# 03PERIPHERALS.net
KiCad netlist of a schematic drawn in Altium Designer
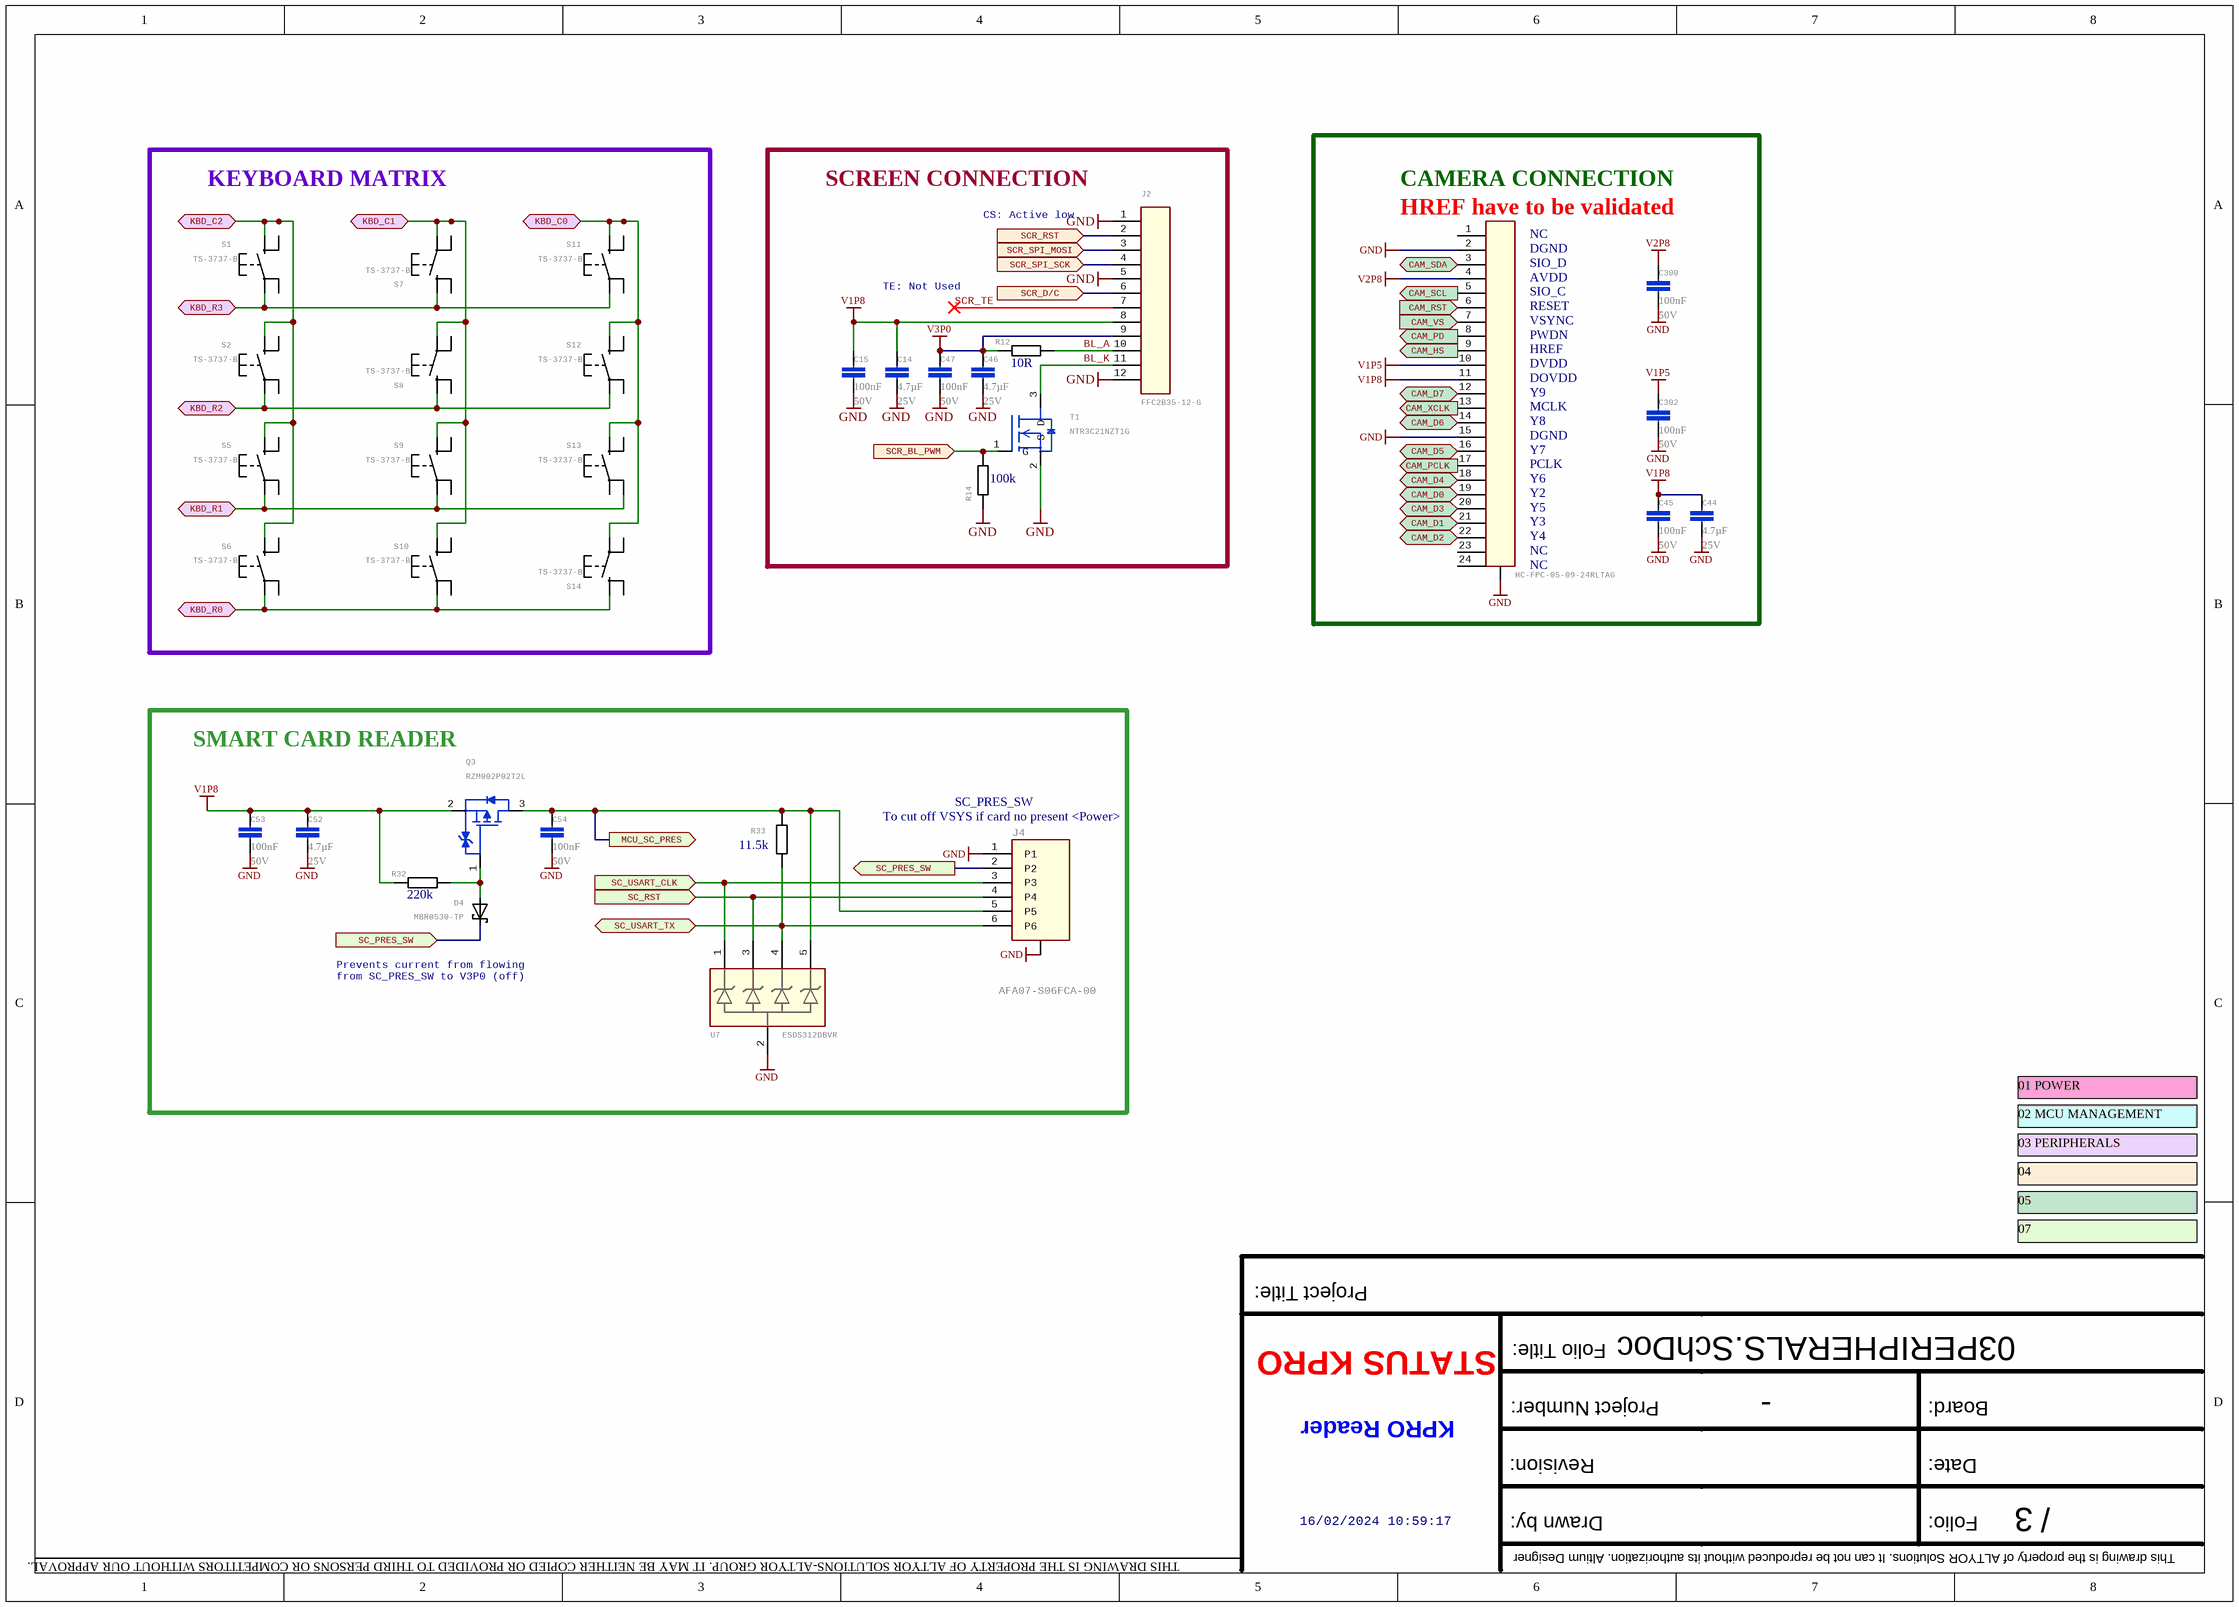
[diagram p0: 03PERIPHERALS.SchDoc]

(export (version "E")
  (design (tool "Eeschema 10.0.6"))
  (components
    (comp (ref "C14")
      (value "0805X475M250CT")
      (footprint "0805 - CAPACITOR")
      (description "CAP X5R 4.7µF 25V ±10% 0805")
      (fields
        (field (name "MANUFACTURER") "WALSIN")
        (field (name "VOLTAGE") "25V")
        (field (name "NAME") "4.7µF")
      )
      (libsource (lib "KCP-2282-600") (part "C-EU-C4.7µF-X5R-6.3V-0805"))
    )
    (comp (ref "C15")
      (value "0402B104K500CT")
      (footprint "0402 - CAPACITOR")
      (description "CAP X7R 100nF 50V ±10% 0402")
      (fields
        (field (name "MANUFACTURER") "WALSIN")
        (field (name "VOLTAGE") "50V")
        (field (name "NAME") "100nF")
      )
      (libsource (lib "") (part "C-EU-C100NF-X7R-16V-0402_1"))
    )
    (comp (ref "C44")
      (value "0805X475M250CT")
      (footprint "0805 - CAPACITOR")
      (description "CAP X5R 4.7µF 25V ±10% 0805")
      (fields
        (field (name "MANUFACTURER") "WALSIN")
        (field (name "VOLTAGE") "25V")
        (field (name "NAME") "4.7µF")
      )
      (libsource (lib "KCP-2282-600") (part "C-EU-C4.7µF-X5R-6.3V-0805"))
    )
    (comp (ref "C45")
      (value "0402B104K500CT")
      (footprint "0402 - CAPACITOR")
      (description "CAP X7R 100nF 50V ±10% 0402")
      (fields
        (field (name "MANUFACTURER") "WALSIN")
        (field (name "VOLTAGE") "50V")
        (field (name "NAME") "100nF")
      )
      (libsource (lib "KCP-2282-600") (part "C-EU-C100NF-X7R-16V-0402"))
    )
    (comp (ref "C46")
      (value "0805X475M250CT")
      (footprint "0805 - CAPACITOR")
      (description "CAP X5R 4.7µF 25V ±10% 0805")
      (fields
        (field (name "MANUFACTURER") "WALSIN")
        (field (name "VOLTAGE") "25V")
        (field (name "NAME") "4.7µF")
      )
      (libsource (lib "KCP-2282-600") (part "C-EU-C4.7µF-X5R-6.3V-0805"))
    )
    (comp (ref "C47")
      (value "0402B104K500CT")
      (footprint "0402 - CAPACITOR")
      (description "CAP X7R 100nF 50V ±10% 0402")
      (fields
        (field (name "MANUFACTURER") "WALSIN")
        (field (name "VOLTAGE") "50V")
        (field (name "NAME") "100nF")
      )
      (libsource (lib "KCP-2282-600") (part "C-EU-C100NF-X7R-16V-0402"))
    )
    (comp (ref "C52")
      (value "0805X475M250CT")
      (footprint "0805 - CAPACITOR")
      (description "CAP X5R 4.7µF 25V ±10% 0805")
      (fields
        (field (name "MANUFACTURER") "WALSIN")
        (field (name "VOLTAGE") "25V")
        (field (name "NAME") "4.7µF")
      )
      (libsource (lib "KCP-2282-600") (part "C-EU-C4.7µF-X5R-6.3V-0805"))
    )
    (comp (ref "C53")
      (value "0402B104K500CT")
      (footprint "0402 - CAPACITOR")
      (description "CAP X7R 100nF 50V ±10% 0402")
      (fields
        (field (name "MANUFACTURER") "WALSIN")
        (field (name "VOLTAGE") "50V")
        (field (name "NAME") "100nF")
      )
      (libsource (lib "KCP-2282-600") (part "C-EU-C100NF-X7R-16V-0402"))
    )
    (comp (ref "C54")
      (value "0402B104K500CT")
      (footprint "0402 - CAPACITOR")
      (description "CAP X7R 100nF 50V ±10% 0402")
      (fields
        (field (name "MANUFACTURER") "WALSIN")
        (field (name "VOLTAGE") "50V")
        (field (name "NAME") "100nF")
      )
      (libsource (lib "KCP-2282-600") (part "C-EU-C100NF-X7R-16V-0402"))
    )
    (comp (ref "C300")
      (value "0402B104K500CT")
      (footprint "0402 - CAPACITOR")
      (description "CAP X7R 100nF 50V ±10% 0402")
      (fields
        (field (name "MANUFACTURER") "WALSIN")
        (field (name "VOLTAGE") "50V")
        (field (name "NAME") "100nF")
      )
      (libsource (lib "KCP-2282-600") (part "C-EU-C100NF-X7R-16V-0402"))
    )
    (comp (ref "C302")
      (value "0402B104K500CT")
      (footprint "0402 - CAPACITOR")
      (description "CAP X7R 100nF 50V ±10% 0402")
      (fields
        (field (name "MANUFACTURER") "WALSIN")
        (field (name "VOLTAGE") "50V")
        (field (name "NAME") "100nF")
      )
      (libsource (lib "KCP-2282-600") (part "C-EU-C100NF-X7R-16V-0402"))
    )
    (comp (ref "D4")
      (value "MBR0530-TP")
      (footprint "SOD123 DIODE INC")
      (description "Schottky Rectifier, 30 V, 500 mA, Single")
      (fields (field (name "MANUFACTURER") "ON SEMI"))
      (libsource (lib "KCP-2282-600") (part "MBR0530T1G"))
    )
    (comp (ref "J2")
      (value "FFC2B35-12-G")
      (footprint "GCT FFC2B35-12-G")
      (description "0.5mm Side entry Flat Flexible Cable Connector, 12pin,  bottom contacts")
      (fields (field (name "MANUFACTURER") "GCT"))
      (libsource (lib "KCP-2282-600") (part "FFC2B35-12-G"))
    )
    (comp (ref "J4")
      (value "AFA07-S06FCA-00")
      (footprint "JUSHUO AFA07-S15FCC-00")
      (description "Connecteurs FFC et FPC FFC/FPC 6 positions, 1mm, right angle, bottom contact")
      (fields (field (name "MANUFACTURER") "JUSHUO"))
      (libsource (lib "KCP-2282-600") (part "JUSHUO AFA07-S15FCC-00"))
    )
    (comp (ref "Q3")
      (value "RZM002P02T2L")
      (footprint "SOT-723")
      (description "MOS P 20V 200mA Rds1.2R")
      (fields (field (name "MANUFACTURER") "ROHM SEMI"))
      (libsource (lib "KCP-2282-600") (part "RZM002P02T2L"))
    )
    (comp (ref "R12")
      (value "RC0402FR-0710RL")
      (footprint "0402 - RESISTOR")
      (description "RES 10R 63mW 1% 0402")
      (fields (field (name "MANUFACTURER") "YAGEO") (field (name "NAME") "10R"))
      (libsource (lib "KCP-2282-600") (part "R-EU-R10-1%-0402"))
    )
    (comp (ref "R14")
      (value "RC0402FR-07100KL")
      (footprint "0402 - RESISTOR")
      (description "RES 100k 63mW 1% 0402")
      (fields (field (name "MANUFACTURER") "YAGEO") (field (name "NAME") "100k"))
      (libsource (lib "KCP-2282-600") (part "R-EU-R100K-1%-0402"))
    )
    (comp (ref "R32")
      (value "RC0402FR-07220KL")
      (footprint "0402 - RESISTOR")
      (description "RES 220k 63mW 1% 0402")
      (fields (field (name "MANUFACTURER") "YAGEO") (field (name "NAME") "220k"))
      (libsource (lib "KCP-2282-600") (part "R-EU-R220K-1%-0402"))
    )
    (comp (ref "R33")
      (value "RC0402FR-0711K5L")
      (footprint "0402 - RESISTOR")
      (description "RES 11k5 63mW 1% 0402")
      (fields (field (name "MANUFACTURER") "YAGEO") (field (name "NAME") "11.5k"))
      (libsource (lib "KCP-2282-600") (part "R-EU-R11.5K-1%-50V-0402"))
    )
    (comp (ref "S1")
      (value "TS-3737-B")
      (footprint "XKB TS3-737")
      (description "Switch 160gr")
      (fields (field (name "MANUFACTURER") "XKB"))
      (libsource (lib "KCP-2282-600") (part "XKB TS3737"))
    )
    (comp (ref "S2")
      (value "TS-3737-B")
      (footprint "XKB TS3-737")
      (description "Switch 160gr")
      (fields (field (name "MANUFACTURER") "XKB"))
      (libsource (lib "KCP-2282-600") (part "XKB TS3737"))
    )
    (comp (ref "S5")
      (value "TS-3737-B")
      (footprint "XKB TS3-737")
      (description "Switch 160gr")
      (fields (field (name "MANUFACTURER") "XKB"))
      (libsource (lib "KCP-2282-600") (part "XKB TS3737"))
    )
    (comp (ref "S6")
      (value "TS-3737-B")
      (footprint "XKB TS3-737")
      (description "Switch 160gr")
      (fields (field (name "MANUFACTURER") "XKB"))
      (libsource (lib "KCP-2282-600") (part "XKB TS3737"))
    )
    (comp (ref "S7")
      (value "TS-3737-B")
      (footprint "XKB TS3-737")
      (description "Switch 160gr")
      (fields (field (name "MANUFACTURER") "XKB"))
      (libsource (lib "KCP-2282-600") (part "XKB TS3737"))
    )
    (comp (ref "S8")
      (value "TS-3737-B")
      (footprint "XKB TS3-737")
      (description "Switch 160gr")
      (fields (field (name "MANUFACTURER") "XKB"))
      (libsource (lib "KCP-2282-600") (part "XKB TS3737"))
    )
    (comp (ref "S9")
      (value "TS-3737-B")
      (footprint "XKB TS3-737")
      (description "Switch 160gr")
      (fields (field (name "MANUFACTURER") "XKB"))
      (libsource (lib "KCP-2282-600") (part "XKB TS3737"))
    )
    (comp (ref "S10")
      (value "TS-3737-B")
      (footprint "XKB TS3-737")
      (description "Switch 160gr")
      (fields (field (name "MANUFACTURER") "XKB"))
      (libsource (lib "KCP-2282-600") (part "XKB TS3737"))
    )
    (comp (ref "S11")
      (value "TS-3737-B")
      (footprint "XKB TS3-737")
      (description "Switch 160gr")
      (fields (field (name "MANUFACTURER") "XKB"))
      (libsource (lib "KCP-2282-600") (part "XKB TS3737"))
    )
    (comp (ref "S12")
      (value "TS-3737-B")
      (footprint "XKB TS3-737")
      (description "Switch 160gr")
      (fields (field (name "MANUFACTURER") "XKB"))
      (libsource (lib "KCP-2282-600") (part "XKB TS3737"))
    )
    (comp (ref "S13")
      (value "TS-3737-B")
      (footprint "XKB TS3-737")
      (description "Switch 160gr")
      (fields (field (name "MANUFACTURER") "XKB"))
      (libsource (lib "KCP-2282-600") (part "XKB TS3737"))
    )
    (comp (ref "S14")
      (value "TS-3737-B")
      (footprint "XKB TS3-737")
      (description "Switch 160gr")
      (fields (field (name "MANUFACTURER") "XKB"))
      (libsource (lib "KCP-2282-600") (part "XKB TS3737"))
    )
    (comp (ref "T1")
      (value "NTR3C21NZT1G")
      (footprint "SOT23-VAR AB")
      (description "MOS N 20V 3.6A Rds24mR - SOT23")
      (fields (field (name "MANUFACTURER") "ON SEMI"))
      (libsource (lib "KCP-2282-600") (part "NTR3C21NZT1G"))
    )
    (comp (ref "U7")
      (value "ESDS312DBVR")
      (footprint "SOT95P270X145-5N")
      (description "3.6V Data-Line Surge and 30kV ESD Protection Diode Array 5-SOT-23 -40 to 125")
      (fields (field (name "MANUFACTURER") "TEXAS"))
      (libsource (lib "KCP-2282-600") (part "ESDS312DBVR"))
    )
    (comp (ref "X1")
      (value "HC-FPC-05-09-24RLTAG")
      (footprint "HCTL HC-FPC-05-09-24RLTAG")
      (description "0.5mm Side entry Flat Flexible Cable Connector, 12pin,  bottom contacts")
      (fields (field (name "MANUFACTURER") "HCTL"))
      (libsource (lib "KCP-2282-600") (part "HCTL HC-FPC-05-09-24RLTAG"))
    )
  )
  (nets
    (net (code "1") (name "/BL_A") (class "Default")
      (node (ref "J2") (pin "10") (pinfunction "10_10") (pintype "passive"))
      (node (ref "R12") (pin "1") (pinfunction "1_1") (pintype "passive"))
    )
    (net (code "2") (name "/BL_K") (class "Default")
      (node (ref "J2") (pin "11") (pinfunction "11_11") (pintype "passive"))
      (node (ref "T1") (pin "3") (pinfunction "D_3") (pintype "passive"))
    )
    (net (code "3") (name "/CAM_D0") (class "Default")
      (node (ref "X1") (pin "19") (pinfunction "19_19") (pintype "passive"))
    )
    (net (code "4") (name "/CAM_D1") (class "Default")
      (node (ref "X1") (pin "21") (pinfunction "21_21") (pintype "passive"))
    )
    (net (code "5") (name "/CAM_D2") (class "Default")
      (node (ref "X1") (pin "22") (pinfunction "22_22") (pintype "passive"))
    )
    (net (code "6") (name "/CAM_D3") (class "Default")
      (node (ref "X1") (pin "20") (pinfunction "20_20") (pintype "passive"))
    )
    (net (code "7") (name "/CAM_D4") (class "Default")
      (node (ref "X1") (pin "18") (pinfunction "18_18") (pintype "passive"))
    )
    (net (code "8") (name "/CAM_D5") (class "Default")
      (node (ref "X1") (pin "16") (pinfunction "16_16") (pintype "passive"))
    )
    (net (code "9") (name "/CAM_D6") (class "Default")
      (node (ref "X1") (pin "14") (pinfunction "14_14") (pintype "passive"))
    )
    (net (code "10") (name "/CAM_D7") (class "Default")
      (node (ref "X1") (pin "12") (pinfunction "12_12") (pintype "passive"))
    )
    (net (code "11") (name "/CAM_HS") (class "Default")
      (node (ref "X1") (pin "9") (pinfunction "9_9") (pintype "passive"))
    )
    (net (code "12") (name "/CAM_PCLK") (class "Default")
      (node (ref "X1") (pin "17") (pinfunction "17_17") (pintype "passive"))
    )
    (net (code "13") (name "/CAM_PD") (class "Default")
      (node (ref "X1") (pin "8") (pinfunction "8_8") (pintype "passive"))
    )
    (net (code "14") (name "/CAM_RST") (class "Default")
      (node (ref "X1") (pin "6") (pinfunction "6_6") (pintype "passive"))
    )
    (net (code "15") (name "/CAM_SCL") (class "Default")
      (node (ref "X1") (pin "5") (pinfunction "5_5") (pintype "passive"))
    )
    (net (code "16") (name "/CAM_SDA") (class "Default")
      (node (ref "X1") (pin "3") (pinfunction "3_3") (pintype "passive"))
    )
    (net (code "17") (name "/CAM_VS") (class "Default")
      (node (ref "X1") (pin "7") (pinfunction "7_7") (pintype "passive"))
    )
    (net (code "18") (name "/CAM_XCLK") (class "Default")
      (node (ref "X1") (pin "13") (pinfunction "13_13") (pintype "passive"))
    )
    (net (code "19") (name "/KBD_C0") (class "Default")
      (node (ref "S11") (pin "A") (pinfunction "A_A") (pintype "passive"))
      (node (ref "S12") (pin "A") (pinfunction "A_A") (pintype "passive"))
      (node (ref "S13") (pin "A") (pinfunction "A_A") (pintype "passive"))
      (node (ref "S14") (pin "C") (pinfunction "C_C") (pintype "passive"))
    )
    (net (code "20") (name "/KBD_C1") (class "Default")
      (node (ref "S10") (pin "A") (pinfunction "A_A") (pintype "passive"))
      (node (ref "S7") (pin "C") (pinfunction "C_C") (pintype "passive"))
      (node (ref "S8") (pin "C") (pinfunction "C_C") (pintype "passive"))
      (node (ref "S9") (pin "A") (pinfunction "A_A") (pintype "passive"))
    )
    (net (code "21") (name "/KBD_C2") (class "Default")
      (node (ref "S1") (pin "A") (pinfunction "A_A") (pintype "passive"))
      (node (ref "S2") (pin "A") (pinfunction "A_A") (pintype "passive"))
      (node (ref "S5") (pin "A") (pinfunction "A_A") (pintype "passive"))
      (node (ref "S6") (pin "A") (pinfunction "A_A") (pintype "passive"))
    )
    (net (code "22") (name "/KBD_R0") (class "Default")
      (node (ref "S10") (pin "C") (pinfunction "C_C") (pintype "passive"))
      (node (ref "S14") (pin "A") (pinfunction "A_A") (pintype "passive"))
      (node (ref "S6") (pin "C") (pinfunction "C_C") (pintype "passive"))
    )
    (net (code "23") (name "/KBD_R1") (class "Default")
      (node (ref "S13") (pin "D") (pinfunction "D_D") (pintype "passive"))
      (node (ref "S5") (pin "C") (pinfunction "C_C") (pintype "passive"))
      (node (ref "S9") (pin "C") (pinfunction "C_C") (pintype "passive"))
    )
    (net (code "24") (name "/KBD_R2") (class "Default")
      (node (ref "S12") (pin "C") (pinfunction "C_C") (pintype "passive"))
      (node (ref "S2") (pin "C") (pinfunction "C_C") (pintype "passive"))
      (node (ref "S8") (pin "A") (pinfunction "A_A") (pintype "passive"))
    )
    (net (code "25") (name "/KBD_R3") (class "Default")
      (node (ref "S1") (pin "C") (pinfunction "C_C") (pintype "passive"))
      (node (ref "S11") (pin "C") (pinfunction "C_C") (pintype "passive"))
      (node (ref "S7") (pin "A") (pinfunction "A_A") (pintype "passive"))
    )
    (net (code "26") (name "/MCU_SC_PRES") (class "Default")
      (node (ref "C54") (pin "1") (pinfunction "1_1") (pintype "passive"))
      (node (ref "J4") (pin "5") (pinfunction "P5_5") (pintype "passive"))
      (node (ref "Q3") (pin "3") (pinfunction "D_3") (pintype "passive"))
      (node (ref "R33") (pin "2") (pinfunction "2_2") (pintype "passive"))
      (node (ref "U7") (pin "5") (pinfunction "5_5") (pintype "passive"))
    )
    (net (code "27") (name "/SCR_BL_PWM") (class "Default")
      (node (ref "R14") (pin "2") (pinfunction "2_2") (pintype "passive"))
      (node (ref "T1") (pin "1") (pinfunction "G_1") (pintype "passive"))
    )
    (net (code "28") (name "/SCR_D{slash}C") (class "Default")
      (node (ref "J2") (pin "6") (pinfunction "6_6") (pintype "passive"))
    )
    (net (code "29") (name "/SCR_RST") (class "Default")
      (node (ref "J2") (pin "2") (pinfunction "2_2") (pintype "passive"))
    )
    (net (code "30") (name "/SCR_SPI_MOSI") (class "Default")
      (node (ref "J2") (pin "3") (pinfunction "3_3") (pintype "passive"))
    )
    (net (code "31") (name "/SCR_SPI_SCK") (class "Default")
      (node (ref "J2") (pin "4") (pinfunction "4_4") (pintype "passive"))
    )
    (net (code "32") (name "/SCR_TE") (class "Default")
      (node (ref "J2") (pin "7") (pinfunction "7_7") (pintype "passive+no_connect"))
    )
    (net (code "33") (name "/SC_PRES_SW") (class "Default")
      (node (ref "D4") (pin "C") (pinfunction "C_C") (pintype "passive"))
      (node (ref "J4") (pin "2") (pinfunction "P2_2") (pintype "passive"))
    )
    (net (code "34") (name "/SC_RST") (class "Default")
      (node (ref "J4") (pin "4") (pinfunction "P4_4") (pintype "passive"))
      (node (ref "U7") (pin "3") (pinfunction "3_3") (pintype "passive"))
    )
    (net (code "35") (name "/SC_USART_CLK") (class "Default")
      (node (ref "J4") (pin "3") (pinfunction "P3_3") (pintype "passive"))
      (node (ref "U7") (pin "1") (pinfunction "1_1") (pintype "passive"))
    )
    (net (code "36") (name "/SC_USART_TX") (class "Default")
      (node (ref "J4") (pin "6") (pinfunction "P6_6") (pintype "passive"))
      (node (ref "R33") (pin "1") (pinfunction "1_1") (pintype "passive"))
      (node (ref "U7") (pin "4") (pinfunction "4_4") (pintype "passive"))
    )
    (net (code "37") (name "GND") (class "Default")
      (node (ref "C14") (pin "2") (pinfunction "2_2") (pintype "passive"))
      (node (ref "C15") (pin "2") (pinfunction "2_2") (pintype "passive"))
      (node (ref "C300") (pin "2") (pinfunction "2_2") (pintype "passive"))
      (node (ref "C302") (pin "2") (pinfunction "2_2") (pintype "passive"))
      (node (ref "C44") (pin "2") (pinfunction "2_2") (pintype "passive"))
      (node (ref "C45") (pin "2") (pinfunction "2_2") (pintype "passive"))
      (node (ref "C46") (pin "2") (pinfunction "2_2") (pintype "passive"))
      (node (ref "C47") (pin "2") (pinfunction "2_2") (pintype "passive"))
      (node (ref "C52") (pin "2") (pinfunction "2_2") (pintype "passive"))
      (node (ref "C53") (pin "2") (pinfunction "2_2") (pintype "passive"))
      (node (ref "C54") (pin "2") (pinfunction "2_2") (pintype "passive"))
      (node (ref "J2") (pin "1") (pinfunction "1_1") (pintype "passive"))
      (node (ref "J2") (pin "12") (pinfunction "12_12") (pintype "passive"))
      (node (ref "J2") (pin "5") (pinfunction "5_5") (pintype "passive"))
      (node (ref "J4") (pin "0") (pinfunction "0_0") (pintype "passive"))
      (node (ref "J4") (pin "1") (pinfunction "P1_1") (pintype "passive"))
      (node (ref "R14") (pin "1") (pinfunction "1_1") (pintype "passive"))
      (node (ref "T1") (pin "2") (pinfunction "S_2") (pintype "passive"))
      (node (ref "U7") (pin "2") (pinfunction "2_2") (pintype "passive"))
      (node (ref "X1") (pin "0") (pinfunction "0_0") (pintype "passive"))
      (node (ref "X1") (pin "15") (pinfunction "15_15") (pintype "passive"))
      (node (ref "X1") (pin "2") (pinfunction "2_2") (pintype "passive"))
    )
    (net (code "38") (name "Net-(Q3-G)") (class "Default")
      (node (ref "D4") (pin "A") (pinfunction "A_A") (pintype "passive"))
      (node (ref "Q3") (pin "1") (pinfunction "G_1") (pintype "passive"))
      (node (ref "R32") (pin "2") (pinfunction "2_2") (pintype "passive"))
    )
    (net (code "39") (name "V1P5") (class "Default")
      (node (ref "C302") (pin "1") (pinfunction "1_1") (pintype "passive"))
      (node (ref "X1") (pin "10") (pinfunction "10_10") (pintype "passive"))
    )
    (net (code "40") (name "V1P8") (class "Default")
      (node (ref "C14") (pin "1") (pinfunction "1_1") (pintype "passive"))
      (node (ref "C15") (pin "1") (pinfunction "1_1") (pintype "passive"))
      (node (ref "C44") (pin "1") (pinfunction "1_1") (pintype "passive"))
      (node (ref "C45") (pin "1") (pinfunction "1_1") (pintype "passive"))
      (node (ref "C52") (pin "1") (pinfunction "1_1") (pintype "passive"))
      (node (ref "C53") (pin "1") (pinfunction "1_1") (pintype "passive"))
      (node (ref "J2") (pin "8") (pinfunction "8_8") (pintype "passive"))
      (node (ref "Q3") (pin "2") (pinfunction "S_2") (pintype "passive"))
      (node (ref "R32") (pin "1") (pinfunction "1_1") (pintype "passive"))
      (node (ref "X1") (pin "11") (pinfunction "11_11") (pintype "passive"))
    )
    (net (code "41") (name "V2P8") (class "Default")
      (node (ref "C300") (pin "1") (pinfunction "1_1") (pintype "passive"))
      (node (ref "X1") (pin "4") (pinfunction "4_4") (pintype "passive"))
    )
    (net (code "42") (name "V3P0") (class "Default")
      (node (ref "C46") (pin "1") (pinfunction "1_1") (pintype "passive"))
      (node (ref "C47") (pin "1") (pinfunction "1_1") (pintype "passive"))
      (node (ref "J2") (pin "9") (pinfunction "9_9") (pintype "passive"))
      (node (ref "R12") (pin "2") (pinfunction "2_2") (pintype "passive"))
    )
    (net (code "43") (name "unconnected-(S1-PadB)") (class "Default")
      (node (ref "S1") (pin "B") (pinfunction "B_B") (pintype "passive"))
    )
    (net (code "44") (name "unconnected-(S1-PadD)") (class "Default")
      (node (ref "S1") (pin "D") (pinfunction "D_D") (pintype "passive"))
    )
    (net (code "45") (name "unconnected-(S2-PadB)") (class "Default")
      (node (ref "S2") (pin "B") (pinfunction "B_B") (pintype "passive"))
    )
    (net (code "46") (name "unconnected-(S2-PadD)") (class "Default")
      (node (ref "S2") (pin "D") (pinfunction "D_D") (pintype "passive"))
    )
    (net (code "47") (name "unconnected-(S5-PadB)") (class "Default")
      (node (ref "S5") (pin "B") (pinfunction "B_B") (pintype "passive"))
    )
    (net (code "48") (name "unconnected-(S5-PadD)") (class "Default")
      (node (ref "S5") (pin "D") (pinfunction "D_D") (pintype "passive"))
    )
    (net (code "49") (name "unconnected-(S6-PadB)") (class "Default")
      (node (ref "S6") (pin "B") (pinfunction "B_B") (pintype "passive"))
    )
    (net (code "50") (name "unconnected-(S6-PadD)") (class "Default")
      (node (ref "S6") (pin "D") (pinfunction "D_D") (pintype "passive"))
    )
    (net (code "51") (name "unconnected-(S7-PadB)") (class "Default")
      (node (ref "S7") (pin "B") (pinfunction "B_B") (pintype "passive"))
    )
    (net (code "52") (name "unconnected-(S7-PadD)") (class "Default")
      (node (ref "S7") (pin "D") (pinfunction "D_D") (pintype "passive"))
    )
    (net (code "53") (name "unconnected-(S8-PadB)") (class "Default")
      (node (ref "S8") (pin "B") (pinfunction "B_B") (pintype "passive"))
    )
    (net (code "54") (name "unconnected-(S8-PadD)") (class "Default")
      (node (ref "S8") (pin "D") (pinfunction "D_D") (pintype "passive"))
    )
    (net (code "55") (name "unconnected-(S9-PadB)") (class "Default")
      (node (ref "S9") (pin "B") (pinfunction "B_B") (pintype "passive"))
    )
    (net (code "56") (name "unconnected-(S9-PadD)") (class "Default")
      (node (ref "S9") (pin "D") (pinfunction "D_D") (pintype "passive"))
    )
    (net (code "57") (name "unconnected-(S10-PadB)") (class "Default")
      (node (ref "S10") (pin "B") (pinfunction "B_B") (pintype "passive"))
    )
    (net (code "58") (name "unconnected-(S10-PadD)") (class "Default")
      (node (ref "S10") (pin "D") (pinfunction "D_D") (pintype "passive"))
    )
    (net (code "59") (name "unconnected-(S11-PadB)") (class "Default")
      (node (ref "S11") (pin "B") (pinfunction "B_B") (pintype "passive"))
    )
    (net (code "60") (name "unconnected-(S11-PadD)") (class "Default")
      (node (ref "S11") (pin "D") (pinfunction "D_D") (pintype "passive"))
    )
    (net (code "61") (name "unconnected-(S12-PadB)") (class "Default")
      (node (ref "S12") (pin "B") (pinfunction "B_B") (pintype "passive"))
    )
    (net (code "62") (name "unconnected-(S12-PadD)") (class "Default")
      (node (ref "S12") (pin "D") (pinfunction "D_D") (pintype "passive"))
    )
    (net (code "63") (name "unconnected-(S13-PadB)") (class "Default")
      (node (ref "S13") (pin "B") (pinfunction "B_B") (pintype "passive"))
    )
    (net (code "64") (name "unconnected-(S13-PadC)") (class "Default")
      (node (ref "S13") (pin "C") (pinfunction "C_C") (pintype "passive"))
    )
    (net (code "65") (name "unconnected-(S14-PadB)") (class "Default")
      (node (ref "S14") (pin "B") (pinfunction "B_B") (pintype "passive"))
    )
    (net (code "66") (name "unconnected-(S14-PadD)") (class "Default")
      (node (ref "S14") (pin "D") (pinfunction "D_D") (pintype "passive"))
    )
    (net (code "67") (name "unconnected-(X1-Pad1)") (class "Default")
      (node (ref "X1") (pin "1") (pinfunction "1_1") (pintype "passive"))
    )
    (net (code "68") (name "unconnected-(X1-Pad23)") (class "Default")
      (node (ref "X1") (pin "23") (pinfunction "23_23") (pintype "passive"))
    )
    (net (code "69") (name "unconnected-(X1-Pad24)") (class "Default")
      (node (ref "X1") (pin "24") (pinfunction "24_24") (pintype "passive"))
    )
  )
)
